# Sensor.net
KiCad netlist of a schematic drawn in Altium Designer
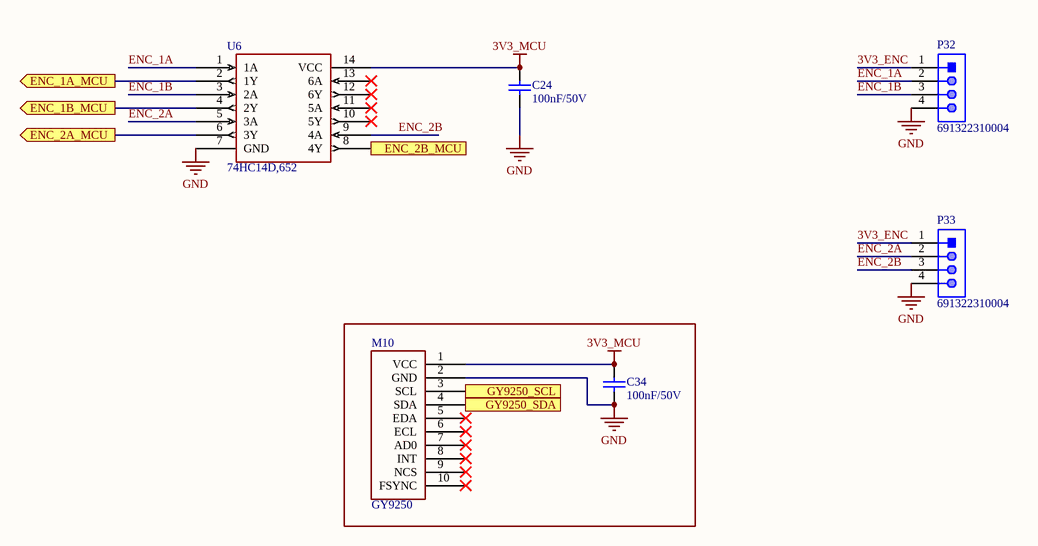
[diagram p0: Sensor.SchDoc]

(export (version "E")
  (design (tool "Eeschema 10.0.6"))
  (components
    (comp (ref "C24")
      (value "100nF/50V")
      (footprint "CAP-SM-0805")
      (description "CAP CER 0.1UF 50V Y5V 0805")
      (fields
        (field (name "MANUFACTURER") "Samsung Electro-Mechanics")
        (field (name "MANUFACTURER PART NUMBER") "CL21F104ZBCNNNC")
      )
      (libsource (lib "Capacitor") (part "Cap-100nF-50V-0805"))
    )
    (comp (ref "C34")
      (value "100nF/50V")
      (footprint "CAP-SM-0805")
      (description "CAP CER 0.1UF 50V Y5V 0805")
      (fields
        (field (name "MANUFACTURER") "Samsung Electro-Mechanics")
        (field (name "MANUFACTURER PART NUMBER") "CL21F104ZBCNNNC")
      )
      (libsource (lib "Capacitor") (part "Cap-100nF-50V-0805"))
    )
    (comp (ref "M10") (value "GY9250") (footprint "GY9250") (libsource (lib "PIF_robot") (part "GY9250")))
    (comp (ref "P32")
      (value "691322310004")
      (footprint "691322310004")
      (description "WR-TBL Serie 322 Horizontal PCB Header, Pluggable, pitch 3.81mm, 4p")
      (fields (field (name "PUBLISHER") "Wurth Elektronik"))
      (libsource (lib "691322310002_Altium_WR-TBL_rev19a") (part "691322310004"))
    )
    (comp (ref "P33")
      (value "691322310004")
      (footprint "691322310004")
      (description "WR-TBL Serie 322 Horizontal PCB Header, Pluggable, pitch 3.81mm, 4p")
      (fields (field (name "PUBLISHER") "Wurth Elektronik"))
      (libsource (lib "691322310002_Altium_WR-TBL_rev19a") (part "691322310004"))
    )
    (comp (ref "U6")
      (value "74HC14D,652")
      (footprint "SOT108-1_NEX")
      (libsource (lib "PIF_robot") (part "74HC14D,652"))
    )
  )
  (nets
    (net (code "1") (name "/3V3_ENC") (class "Default")
      (node (ref "P32") (pin "1") (pinfunction "1_1") (pintype "passive"))
      (node (ref "P33") (pin "1") (pinfunction "1_1") (pintype "passive"))
    )
    (net (code "2") (name "/ENC_1A") (class "Default")
      (node (ref "P32") (pin "2") (pinfunction "2_2") (pintype "passive"))
      (node (ref "U6") (pin "1") (pinfunction "1A_1") (pintype "input"))
    )
    (net (code "3") (name "/ENC_1A_MCU") (class "Default")
      (node (ref "U6") (pin "2") (pinfunction "1Y_2") (pintype "output"))
    )
    (net (code "4") (name "/ENC_1B") (class "Default")
      (node (ref "P32") (pin "3") (pinfunction "3_3") (pintype "passive"))
      (node (ref "U6") (pin "3") (pinfunction "2A_3") (pintype "input"))
    )
    (net (code "5") (name "/ENC_1B_MCU") (class "Default")
      (node (ref "U6") (pin "4") (pinfunction "2Y_4") (pintype "output"))
    )
    (net (code "6") (name "/ENC_2A") (class "Default")
      (node (ref "P33") (pin "2") (pinfunction "2_2") (pintype "passive"))
      (node (ref "U6") (pin "5") (pinfunction "3A_5") (pintype "input"))
    )
    (net (code "7") (name "/ENC_2A_MCU") (class "Default")
      (node (ref "U6") (pin "6") (pinfunction "3Y_6") (pintype "output"))
    )
    (net (code "8") (name "/ENC_2B") (class "Default")
      (node (ref "P33") (pin "3") (pinfunction "3_3") (pintype "passive"))
      (node (ref "U6") (pin "9") (pinfunction "4A_9") (pintype "input"))
    )
    (net (code "9") (name "/ENC_2B_MCU") (class "Default")
      (node (ref "U6") (pin "8") (pinfunction "4Y_8") (pintype "output"))
    )
    (net (code "10") (name "/GY9250_SCL") (class "Default")
      (node (ref "M10") (pin "3") (pinfunction "SCL_3") (pintype "passive"))
    )
    (net (code "11") (name "/GY9250_SDA") (class "Default")
      (node (ref "M10") (pin "4") (pinfunction "SDA_4") (pintype "passive"))
    )
    (net (code "12") (name "3V3_MCU") (class "Default")
      (node (ref "C24") (pin "2") (pinfunction "2_2") (pintype "passive"))
      (node (ref "C34") (pin "2") (pinfunction "2_2") (pintype "passive"))
      (node (ref "M10") (pin "1") (pinfunction "VCC_1") (pintype "passive"))
      (node (ref "U6") (pin "14") (pinfunction "VCC_14") (pintype "power_in"))
    )
    (net (code "13") (name "GND") (class "Default")
      (node (ref "C24") (pin "1") (pinfunction "1_1") (pintype "passive"))
      (node (ref "C34") (pin "1") (pinfunction "1_1") (pintype "passive"))
      (node (ref "M10") (pin "2") (pinfunction "GND_2") (pintype "passive"))
      (node (ref "P32") (pin "4") (pinfunction "4_4") (pintype "passive"))
      (node (ref "P33") (pin "4") (pinfunction "4_4") (pintype "passive"))
      (node (ref "U6") (pin "7") (pinfunction "GND_7") (pintype "power_in"))
    )
    (net (code "14") (name "unconnected-(M10-AD0-Pad7)") (class "Default")
      (node (ref "M10") (pin "7") (pinfunction "AD0_7") (pintype "passive+no_connect"))
    )
    (net (code "15") (name "unconnected-(M10-ECL-Pad6)") (class "Default")
      (node (ref "M10") (pin "6") (pinfunction "ECL_6") (pintype "passive+no_connect"))
    )
    (net (code "16") (name "unconnected-(M10-EDA-Pad5)") (class "Default")
      (node (ref "M10") (pin "5") (pinfunction "EDA_5") (pintype "passive+no_connect"))
    )
    (net (code "17") (name "unconnected-(M10-FSYNC-Pad10)") (class "Default")
      (node (ref "M10") (pin "10") (pinfunction "FSYNC_10") (pintype "passive+no_connect"))
    )
    (net (code "18") (name "unconnected-(M10-INT-Pad8)") (class "Default")
      (node (ref "M10") (pin "8") (pinfunction "INT_8") (pintype "passive+no_connect"))
    )
    (net (code "19") (name "unconnected-(M10-NCS-Pad9)") (class "Default")
      (node (ref "M10") (pin "9") (pinfunction "NCS_9") (pintype "passive+no_connect"))
    )
    (net (code "20") (name "unconnected-(U6-5A-Pad11)") (class "Default")
      (node (ref "U6") (pin "11") (pinfunction "5A_11") (pintype "input+no_connect"))
    )
    (net (code "21") (name "unconnected-(U6-5Y-Pad10)") (class "Default")
      (node (ref "U6") (pin "10") (pinfunction "5Y_10") (pintype "output+no_connect"))
    )
    (net (code "22") (name "unconnected-(U6-6A-Pad13)") (class "Default")
      (node (ref "U6") (pin "13") (pinfunction "6A_13") (pintype "input+no_connect"))
    )
    (net (code "23") (name "unconnected-(U6-6Y-Pad12)") (class "Default")
      (node (ref "U6") (pin "12") (pinfunction "6Y_12") (pintype "output+no_connect"))
    )
  )
)
